# Sch3AllChannelControl.net
KiCad netlist of a schematic drawn in Altium Designer
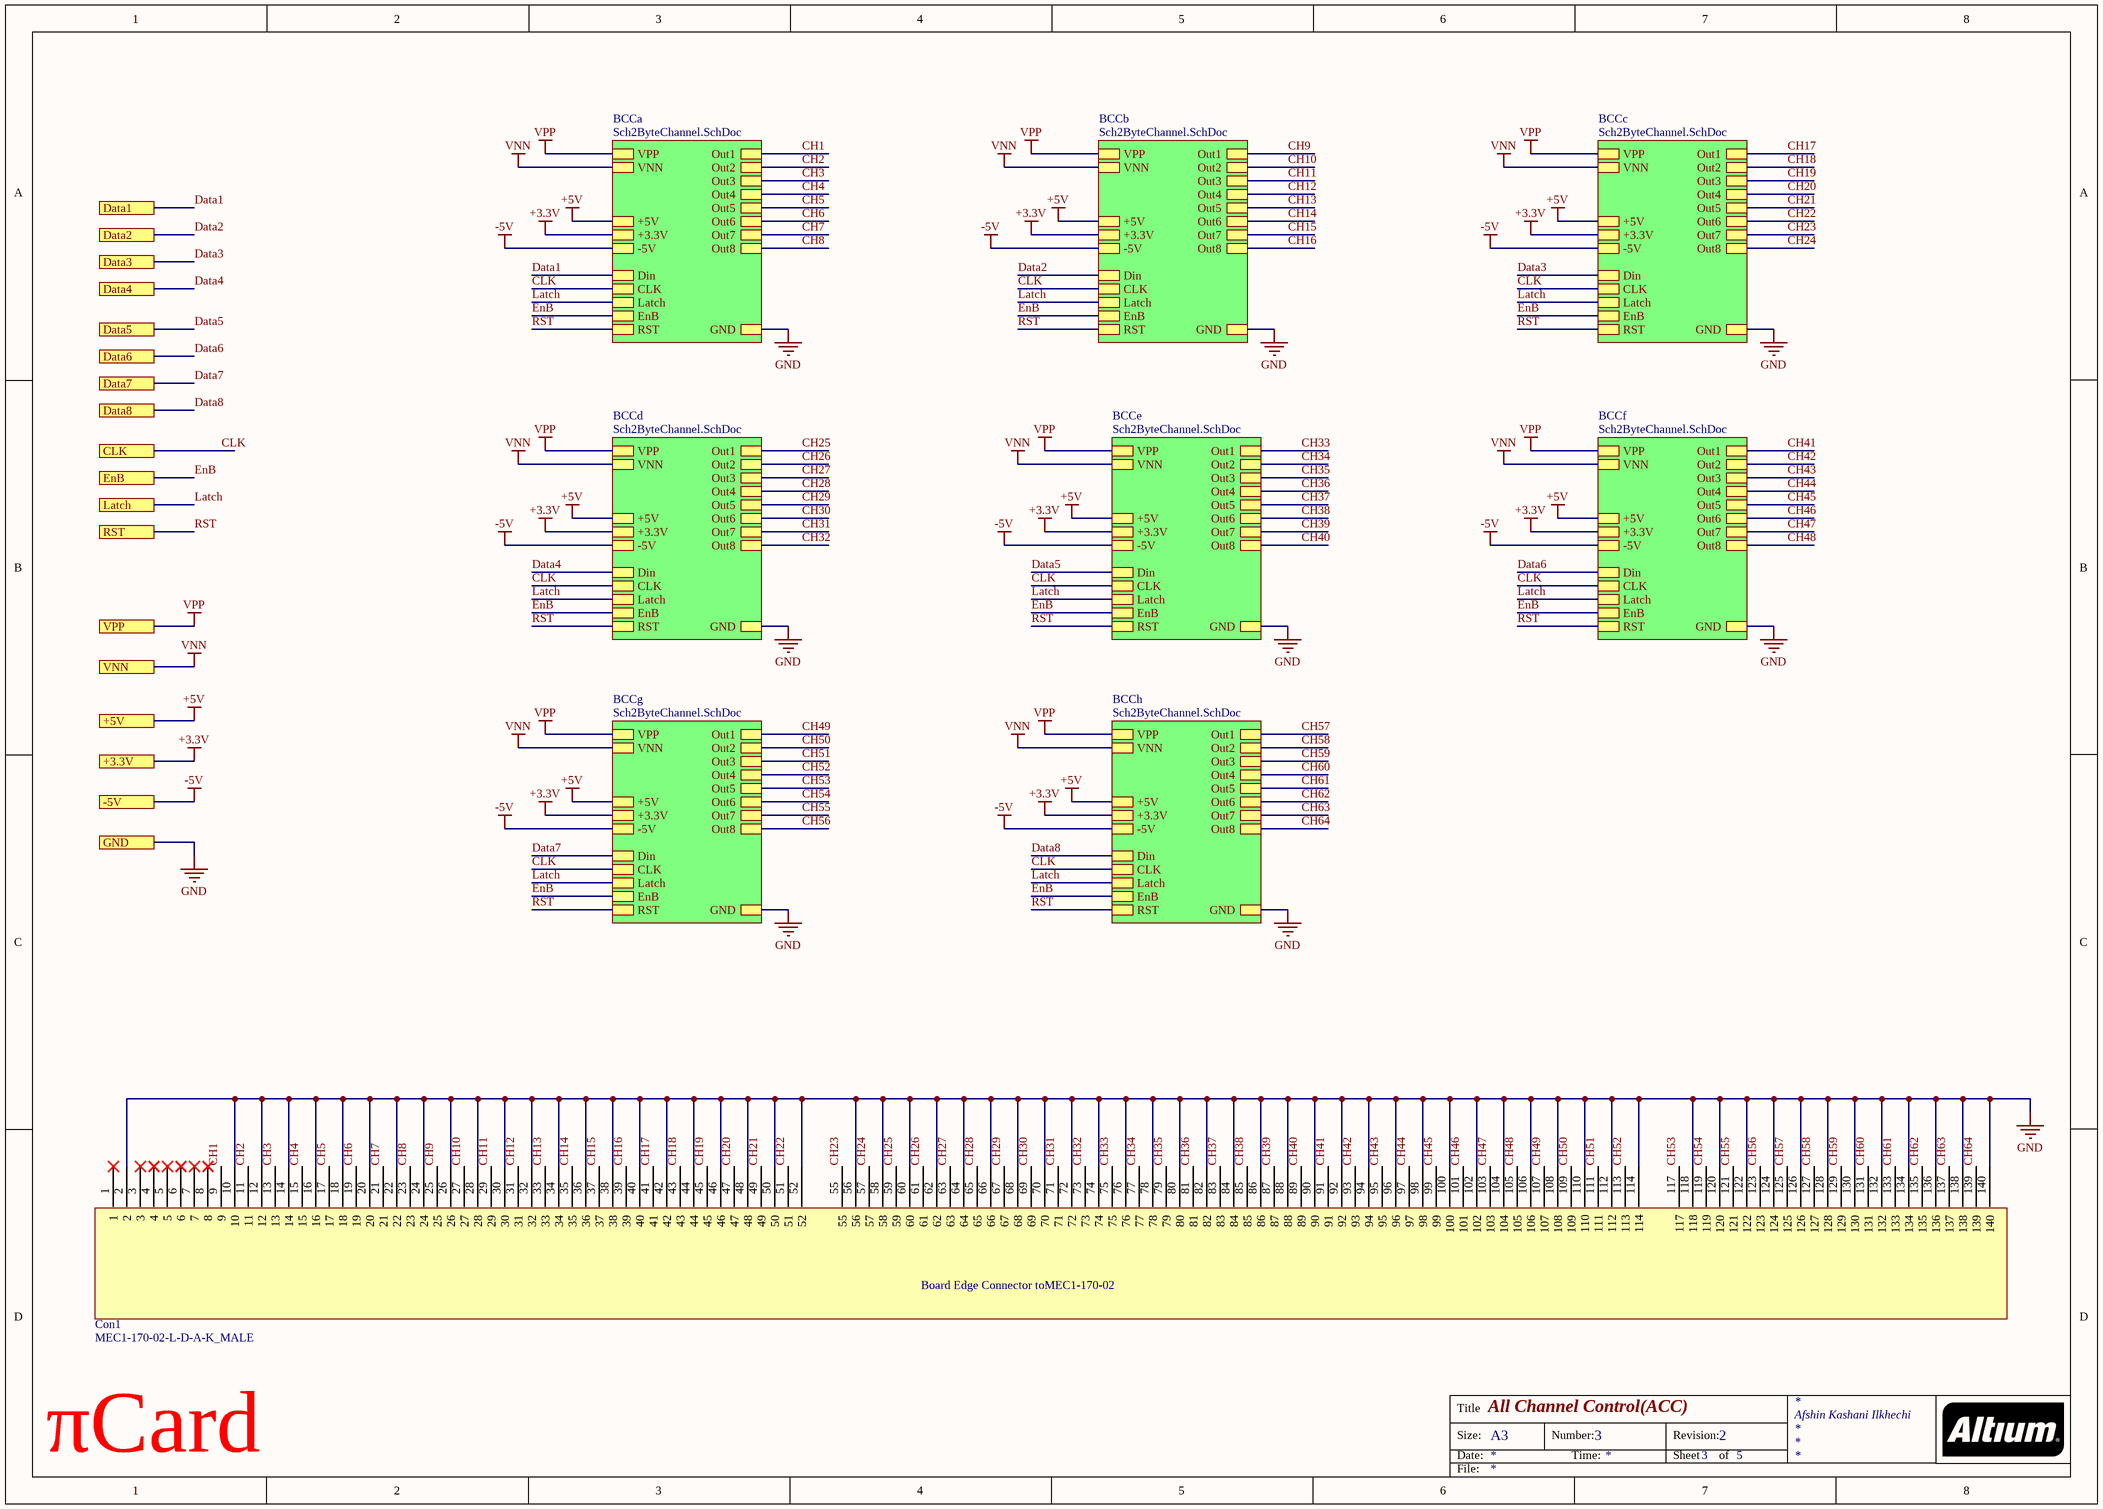
[diagram p0: Sch3AllChannelControl.SchDoc]

(export (version "E")
  (design (tool "Eeschema 10.0.6"))
  (components
    (comp (ref "Con1")
      (value "MEC1-170-02-L-D-A-K_MALE")
      (footprint "MEC1-170-02-L-D-A-K_MALE")
      (libsource (lib "Afshin Library") (part "MEC1-170-02-L-D-A-K_MALE"))
    )
  )
  (nets
    (net (code "4") (name "/CH1") (class "Default")
      (node (ref "Con1") (pin "9") (pinfunction "9_9") (pintype "passive"))
    )
    (net (code "5") (name "/CH2") (class "Default")
      (node (ref "Con1") (pin "11") (pinfunction "11_11") (pintype "passive"))
    )
    (net (code "6") (name "/CH3") (class "Default")
      (node (ref "Con1") (pin "13") (pinfunction "13_13") (pintype "passive"))
    )
    (net (code "7") (name "/CH4") (class "Default")
      (node (ref "Con1") (pin "15") (pinfunction "15_15") (pintype "passive"))
    )
    (net (code "8") (name "/CH5") (class "Default")
      (node (ref "Con1") (pin "17") (pinfunction "17_17") (pintype "passive"))
    )
    (net (code "9") (name "/CH6") (class "Default")
      (node (ref "Con1") (pin "19") (pinfunction "19_19") (pintype "passive"))
    )
    (net (code "10") (name "/CH7") (class "Default")
      (node (ref "Con1") (pin "21") (pinfunction "21_21") (pintype "passive"))
    )
    (net (code "11") (name "/CH8") (class "Default")
      (node (ref "Con1") (pin "23") (pinfunction "23_23") (pintype "passive"))
    )
    (net (code "12") (name "/CH9") (class "Default")
      (node (ref "Con1") (pin "25") (pinfunction "25_25") (pintype "passive"))
    )
    (net (code "13") (name "/CH10") (class "Default")
      (node (ref "Con1") (pin "27") (pinfunction "27_27") (pintype "passive"))
    )
    (net (code "14") (name "/CH11") (class "Default")
      (node (ref "Con1") (pin "29") (pinfunction "29_29") (pintype "passive"))
    )
    (net (code "15") (name "/CH12") (class "Default")
      (node (ref "Con1") (pin "31") (pinfunction "31_31") (pintype "passive"))
    )
    (net (code "16") (name "/CH13") (class "Default")
      (node (ref "Con1") (pin "33") (pinfunction "33_33") (pintype "passive"))
    )
    (net (code "17") (name "/CH14") (class "Default")
      (node (ref "Con1") (pin "35") (pinfunction "35_35") (pintype "passive"))
    )
    (net (code "18") (name "/CH15") (class "Default")
      (node (ref "Con1") (pin "37") (pinfunction "37_37") (pintype "passive"))
    )
    (net (code "19") (name "/CH16") (class "Default")
      (node (ref "Con1") (pin "39") (pinfunction "39_39") (pintype "passive"))
    )
    (net (code "20") (name "/CH17") (class "Default")
      (node (ref "Con1") (pin "41") (pinfunction "41_41") (pintype "passive"))
    )
    (net (code "21") (name "/CH18") (class "Default")
      (node (ref "Con1") (pin "43") (pinfunction "43_43") (pintype "passive"))
    )
    (net (code "22") (name "/CH19") (class "Default")
      (node (ref "Con1") (pin "45") (pinfunction "45_45") (pintype "passive"))
    )
    (net (code "23") (name "/CH20") (class "Default")
      (node (ref "Con1") (pin "47") (pinfunction "47_47") (pintype "passive"))
    )
    (net (code "24") (name "/CH21") (class "Default")
      (node (ref "Con1") (pin "49") (pinfunction "49_49") (pintype "passive"))
    )
    (net (code "25") (name "/CH22") (class "Default")
      (node (ref "Con1") (pin "51") (pinfunction "51_51") (pintype "passive"))
    )
    (net (code "26") (name "/CH23") (class "Default")
      (node (ref "Con1") (pin "55") (pinfunction "55_55") (pintype "passive"))
    )
    (net (code "27") (name "/CH24") (class "Default")
      (node (ref "Con1") (pin "57") (pinfunction "57_57") (pintype "passive"))
    )
    (net (code "28") (name "/CH25") (class "Default")
      (node (ref "Con1") (pin "59") (pinfunction "59_59") (pintype "passive"))
    )
    (net (code "29") (name "/CH26") (class "Default")
      (node (ref "Con1") (pin "61") (pinfunction "61_61") (pintype "passive"))
    )
    (net (code "30") (name "/CH27") (class "Default")
      (node (ref "Con1") (pin "63") (pinfunction "63_63") (pintype "passive"))
    )
    (net (code "31") (name "/CH28") (class "Default")
      (node (ref "Con1") (pin "65") (pinfunction "65_65") (pintype "passive"))
    )
    (net (code "32") (name "/CH29") (class "Default")
      (node (ref "Con1") (pin "67") (pinfunction "67_67") (pintype "passive"))
    )
    (net (code "33") (name "/CH30") (class "Default")
      (node (ref "Con1") (pin "69") (pinfunction "69_69") (pintype "passive"))
    )
    (net (code "34") (name "/CH31") (class "Default")
      (node (ref "Con1") (pin "71") (pinfunction "71_71") (pintype "passive"))
    )
    (net (code "35") (name "/CH32") (class "Default")
      (node (ref "Con1") (pin "73") (pinfunction "73_73") (pintype "passive"))
    )
    (net (code "36") (name "/CH33") (class "Default")
      (node (ref "Con1") (pin "75") (pinfunction "75_75") (pintype "passive"))
    )
    (net (code "37") (name "/CH34") (class "Default")
      (node (ref "Con1") (pin "77") (pinfunction "77_77") (pintype "passive"))
    )
    (net (code "38") (name "/CH35") (class "Default")
      (node (ref "Con1") (pin "79") (pinfunction "79_79") (pintype "passive"))
    )
    (net (code "39") (name "/CH36") (class "Default")
      (node (ref "Con1") (pin "81") (pinfunction "81_81") (pintype "passive"))
    )
    (net (code "40") (name "/CH37") (class "Default")
      (node (ref "Con1") (pin "83") (pinfunction "83_83") (pintype "passive"))
    )
    (net (code "41") (name "/CH38") (class "Default")
      (node (ref "Con1") (pin "85") (pinfunction "85_85") (pintype "passive"))
    )
    (net (code "42") (name "/CH39") (class "Default")
      (node (ref "Con1") (pin "87") (pinfunction "87_87") (pintype "passive"))
    )
    (net (code "43") (name "/CH40") (class "Default")
      (node (ref "Con1") (pin "89") (pinfunction "89_89") (pintype "passive"))
    )
    (net (code "44") (name "/CH41") (class "Default")
      (node (ref "Con1") (pin "91") (pinfunction "91_91") (pintype "passive"))
    )
    (net (code "45") (name "/CH42") (class "Default")
      (node (ref "Con1") (pin "93") (pinfunction "93_93") (pintype "passive"))
    )
    (net (code "46") (name "/CH43") (class "Default")
      (node (ref "Con1") (pin "95") (pinfunction "95_95") (pintype "passive"))
    )
    (net (code "47") (name "/CH44") (class "Default")
      (node (ref "Con1") (pin "97") (pinfunction "97_97") (pintype "passive"))
    )
    (net (code "48") (name "/CH45") (class "Default")
      (node (ref "Con1") (pin "99") (pinfunction "99_99") (pintype "passive"))
    )
    (net (code "49") (name "/CH46") (class "Default")
      (node (ref "Con1") (pin "101") (pinfunction "101_101") (pintype "passive"))
    )
    (net (code "50") (name "/CH47") (class "Default")
      (node (ref "Con1") (pin "103") (pinfunction "103_103") (pintype "passive"))
    )
    (net (code "51") (name "/CH48") (class "Default")
      (node (ref "Con1") (pin "105") (pinfunction "105_105") (pintype "passive"))
    )
    (net (code "52") (name "/CH49") (class "Default")
      (node (ref "Con1") (pin "107") (pinfunction "107_107") (pintype "passive"))
    )
    (net (code "53") (name "/CH50") (class "Default")
      (node (ref "Con1") (pin "109") (pinfunction "109_109") (pintype "passive"))
    )
    (net (code "54") (name "/CH51") (class "Default")
      (node (ref "Con1") (pin "111") (pinfunction "111_111") (pintype "passive"))
    )
    (net (code "55") (name "/CH52") (class "Default")
      (node (ref "Con1") (pin "113") (pinfunction "113_113") (pintype "passive"))
    )
    (net (code "56") (name "/CH53") (class "Default")
      (node (ref "Con1") (pin "117") (pinfunction "117_117") (pintype "passive"))
    )
    (net (code "57") (name "/CH54") (class "Default")
      (node (ref "Con1") (pin "119") (pinfunction "119_119") (pintype "passive"))
    )
    (net (code "58") (name "/CH55") (class "Default")
      (node (ref "Con1") (pin "121") (pinfunction "121_121") (pintype "passive"))
    )
    (net (code "59") (name "/CH56") (class "Default")
      (node (ref "Con1") (pin "123") (pinfunction "123_123") (pintype "passive"))
    )
    (net (code "60") (name "/CH57") (class "Default")
      (node (ref "Con1") (pin "125") (pinfunction "125_125") (pintype "passive"))
    )
    (net (code "61") (name "/CH58") (class "Default")
      (node (ref "Con1") (pin "127") (pinfunction "127_127") (pintype "passive"))
    )
    (net (code "62") (name "/CH59") (class "Default")
      (node (ref "Con1") (pin "129") (pinfunction "129_129") (pintype "passive"))
    )
    (net (code "63") (name "/CH60") (class "Default")
      (node (ref "Con1") (pin "131") (pinfunction "131_131") (pintype "passive"))
    )
    (net (code "64") (name "/CH61") (class "Default")
      (node (ref "Con1") (pin "133") (pinfunction "133_133") (pintype "passive"))
    )
    (net (code "65") (name "/CH62") (class "Default")
      (node (ref "Con1") (pin "135") (pinfunction "135_135") (pintype "passive"))
    )
    (net (code "66") (name "/CH63") (class "Default")
      (node (ref "Con1") (pin "137") (pinfunction "137_137") (pintype "passive"))
    )
    (net (code "67") (name "/CH64") (class "Default")
      (node (ref "Con1") (pin "139") (pinfunction "139_139") (pintype "passive"))
    )
    (net (code "80") (name "GND") (class "Default")
      (node (ref "Con1") (pin "10") (pinfunction "10_10") (pintype "passive"))
      (node (ref "Con1") (pin "100") (pinfunction "100_100") (pintype "passive"))
      (node (ref "Con1") (pin "102") (pinfunction "102_102") (pintype "passive"))
      (node (ref "Con1") (pin "104") (pinfunction "104_104") (pintype "passive"))
      (node (ref "Con1") (pin "106") (pinfunction "106_106") (pintype "passive"))
      (node (ref "Con1") (pin "108") (pinfunction "108_108") (pintype "passive"))
      (node (ref "Con1") (pin "110") (pinfunction "110_110") (pintype "passive"))
      (node (ref "Con1") (pin "112") (pinfunction "112_112") (pintype "passive"))
      (node (ref "Con1") (pin "114") (pinfunction "114_114") (pintype "passive"))
      (node (ref "Con1") (pin "118") (pinfunction "118_118") (pintype "passive"))
      (node (ref "Con1") (pin "12") (pinfunction "12_12") (pintype "passive"))
      (node (ref "Con1") (pin "120") (pinfunction "120_120") (pintype "passive"))
      (node (ref "Con1") (pin "122") (pinfunction "122_122") (pintype "passive"))
      (node (ref "Con1") (pin "124") (pinfunction "124_124") (pintype "passive"))
      (node (ref "Con1") (pin "126") (pinfunction "126_126") (pintype "passive"))
      (node (ref "Con1") (pin "128") (pinfunction "128_128") (pintype "passive"))
      (node (ref "Con1") (pin "130") (pinfunction "130_130") (pintype "passive"))
      (node (ref "Con1") (pin "132") (pinfunction "132_132") (pintype "passive"))
      (node (ref "Con1") (pin "134") (pinfunction "134_134") (pintype "passive"))
      (node (ref "Con1") (pin "136") (pinfunction "136_136") (pintype "passive"))
      (node (ref "Con1") (pin "138") (pinfunction "138_138") (pintype "passive"))
      (node (ref "Con1") (pin "14") (pinfunction "14_14") (pintype "passive"))
      (node (ref "Con1") (pin "140") (pinfunction "140_140") (pintype "passive"))
      (node (ref "Con1") (pin "16") (pinfunction "16_16") (pintype "passive"))
      (node (ref "Con1") (pin "18") (pinfunction "18_18") (pintype "passive"))
      (node (ref "Con1") (pin "2") (pinfunction "2_2") (pintype "passive"))
      (node (ref "Con1") (pin "20") (pinfunction "20_20") (pintype "passive"))
      (node (ref "Con1") (pin "22") (pinfunction "22_22") (pintype "passive"))
      (node (ref "Con1") (pin "24") (pinfunction "24_24") (pintype "passive"))
      (node (ref "Con1") (pin "26") (pinfunction "26_26") (pintype "passive"))
      (node (ref "Con1") (pin "28") (pinfunction "28_28") (pintype "passive"))
      (node (ref "Con1") (pin "30") (pinfunction "30_30") (pintype "passive"))
      (node (ref "Con1") (pin "32") (pinfunction "32_32") (pintype "passive"))
      (node (ref "Con1") (pin "34") (pinfunction "34_34") (pintype "passive"))
      (node (ref "Con1") (pin "36") (pinfunction "36_36") (pintype "passive"))
      (node (ref "Con1") (pin "38") (pinfunction "38_38") (pintype "passive"))
      (node (ref "Con1") (pin "40") (pinfunction "40_40") (pintype "passive"))
      (node (ref "Con1") (pin "42") (pinfunction "42_42") (pintype "passive"))
      (node (ref "Con1") (pin "44") (pinfunction "44_44") (pintype "passive"))
      (node (ref "Con1") (pin "46") (pinfunction "46_46") (pintype "passive"))
      (node (ref "Con1") (pin "48") (pinfunction "48_48") (pintype "passive"))
      (node (ref "Con1") (pin "50") (pinfunction "50_50") (pintype "passive"))
      (node (ref "Con1") (pin "52") (pinfunction "52_52") (pintype "passive"))
      (node (ref "Con1") (pin "56") (pinfunction "56_56") (pintype "passive"))
      (node (ref "Con1") (pin "58") (pinfunction "58_58") (pintype "passive"))
      (node (ref "Con1") (pin "60") (pinfunction "60_60") (pintype "passive"))
      (node (ref "Con1") (pin "62") (pinfunction "62_62") (pintype "passive"))
      (node (ref "Con1") (pin "64") (pinfunction "64_64") (pintype "passive"))
      (node (ref "Con1") (pin "66") (pinfunction "66_66") (pintype "passive"))
      (node (ref "Con1") (pin "68") (pinfunction "68_68") (pintype "passive"))
      (node (ref "Con1") (pin "70") (pinfunction "70_70") (pintype "passive"))
      (node (ref "Con1") (pin "72") (pinfunction "72_72") (pintype "passive"))
      (node (ref "Con1") (pin "74") (pinfunction "74_74") (pintype "passive"))
      (node (ref "Con1") (pin "76") (pinfunction "76_76") (pintype "passive"))
      (node (ref "Con1") (pin "78") (pinfunction "78_78") (pintype "passive"))
      (node (ref "Con1") (pin "80") (pinfunction "80_80") (pintype "passive"))
      (node (ref "Con1") (pin "82") (pinfunction "82_82") (pintype "passive"))
      (node (ref "Con1") (pin "84") (pinfunction "84_84") (pintype "passive"))
      (node (ref "Con1") (pin "86") (pinfunction "86_86") (pintype "passive"))
      (node (ref "Con1") (pin "88") (pinfunction "88_88") (pintype "passive"))
      (node (ref "Con1") (pin "90") (pinfunction "90_90") (pintype "passive"))
      (node (ref "Con1") (pin "92") (pinfunction "92_92") (pintype "passive"))
      (node (ref "Con1") (pin "94") (pinfunction "94_94") (pintype "passive"))
      (node (ref "Con1") (pin "96") (pinfunction "96_96") (pintype "passive"))
      (node (ref "Con1") (pin "98") (pinfunction "98_98") (pintype "passive"))
    )
    (net (code "83") (name "unconnected-(Con1-Pad1)") (class "Default")
      (node (ref "Con1") (pin "1") (pinfunction "1_1") (pintype "passive+no_connect"))
    )
    (net (code "84") (name "unconnected-(Con1-Pad3)") (class "Default")
      (node (ref "Con1") (pin "3") (pinfunction "3_3") (pintype "passive+no_connect"))
    )
    (net (code "85") (name "unconnected-(Con1-Pad4)") (class "Default")
      (node (ref "Con1") (pin "4") (pinfunction "4_4") (pintype "passive+no_connect"))
    )
    (net (code "86") (name "unconnected-(Con1-Pad5)") (class "Default")
      (node (ref "Con1") (pin "5") (pinfunction "5_5") (pintype "passive+no_connect"))
    )
    (net (code "87") (name "unconnected-(Con1-Pad6)") (class "Default")
      (node (ref "Con1") (pin "6") (pinfunction "6_6") (pintype "passive+no_connect"))
    )
    (net (code "88") (name "unconnected-(Con1-Pad7)") (class "Default")
      (node (ref "Con1") (pin "7") (pinfunction "7_7") (pintype "passive+no_connect"))
    )
    (net (code "89") (name "unconnected-(Con1-Pad8)") (class "Default")
      (node (ref "Con1") (pin "8") (pinfunction "8_8") (pintype "passive+no_connect"))
    )
  )
)
